# FLC-PCR_PCB_rev_1.net
KiCad netlist of a schematic drawn in EAGLE
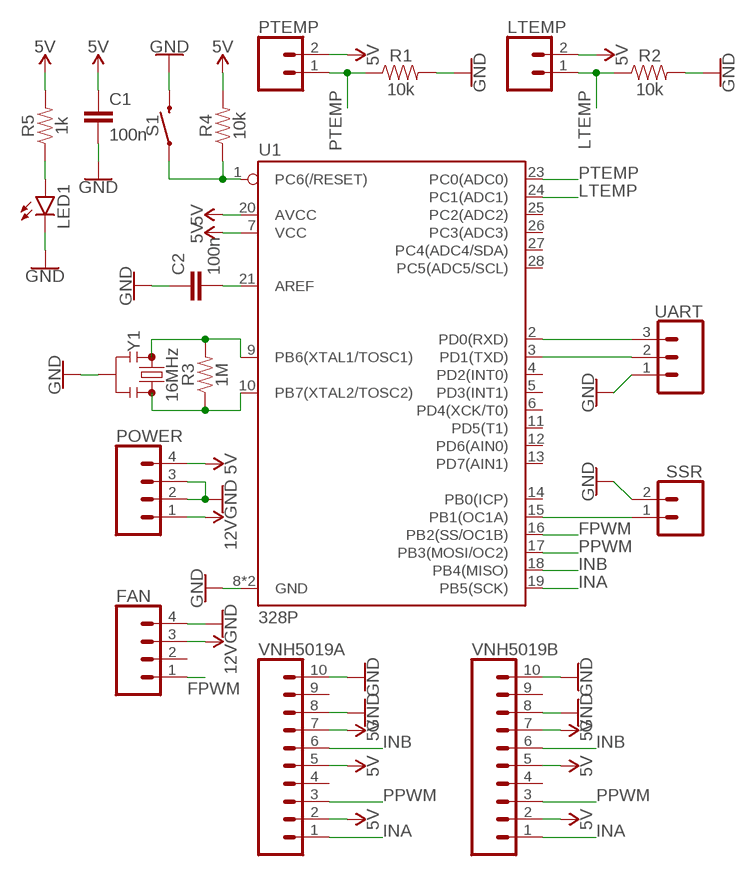
[diagram p0: schematic, sheet 1]

(export (version "E")
  (design (tool "Eeschema 10.0.6"))
  (components
    (comp (ref "C1")
      (value "100n")
      (footprint "eagle-import:C025-050X050")
      (libsource (lib "eagle-import") (part "C-EU025-050X050"))
    )
    (comp (ref "C2")
      (value "100n")
      (footprint "eagle-import:C025-050X050")
      (libsource (lib "eagle-import") (part "C-EU025-050X050"))
    )
    (comp (ref "FAN")
      (value "CONN_04PTH")
      (footprint "eagle-import:1X04")
      (libsource (lib "eagle-import") (part "CONN_04PTH"))
    )
    (comp (ref "LED1")
      (value "LED5MM")
      (footprint "eagle-import:LED5MM")
      (libsource (lib "eagle-import") (part "LED5MM"))
    )
    (comp (ref "LTEMP")
      (value "CONN_02")
      (footprint "eagle-import:1X02")
      (libsource (lib "eagle-import") (part "CONN_02"))
    )
    (comp (ref "POWER")
      (value "CONN_04PTH")
      (footprint "eagle-import:1X04")
      (libsource (lib "eagle-import") (part "CONN_04PTH"))
    )
    (comp (ref "PTEMP")
      (value "CONN_02")
      (footprint "eagle-import:1X02")
      (libsource (lib "eagle-import") (part "CONN_02"))
    )
    (comp (ref "R1")
      (value "10k")
      (footprint "eagle-import:AXIAL-0.3")
      (libsource (lib "eagle-import") (part "10KOHM-HORIZ-1/4W-1%"))
    )
    (comp (ref "R2")
      (value "10k")
      (footprint "eagle-import:AXIAL-0.3")
      (libsource (lib "eagle-import") (part "10KOHM-HORIZ-1/4W-1%"))
    )
    (comp (ref "R3")
      (value "1M")
      (footprint "eagle-import:AXIAL-0.3")
      (libsource (lib "eagle-import") (part "1MOHM-HORIZ-1/4W-5%"))
    )
    (comp (ref "R4")
      (value "10k")
      (footprint "eagle-import:AXIAL-0.3")
      (libsource (lib "eagle-import") (part "10KOHM-HORIZ-1/4W-1%"))
    )
    (comp (ref "R5")
      (value "1k")
      (footprint "eagle-import:AXIAL-0.3")
      (libsource (lib "eagle-import") (part "1KOHM-HORIZ-1/4W-1%"))
    )
    (comp (ref "S1")
      (value "MOMENTARY-SWITCH-SPST-PTH-6.0MM")
      (footprint "eagle-import:TACTILE_SWITCH_PTH_6.0MM")
      (libsource (lib "eagle-import") (part "MOMENTARY-SWITCH-SPST-PTH-6.0MM"))
    )
    (comp (ref "SSR")
      (value "CONN_02")
      (footprint "eagle-import:1X02")
      (libsource (lib "eagle-import") (part "CONN_02"))
    )
    (comp (ref "U1")
      (value "328P")
      (footprint "eagle-import:DIP28")
      (libsource (lib "eagle-import") (part "ATMEGA328P_PDIP"))
    )
    (comp (ref "UART")
      (value "CONN_03")
      (footprint "eagle-import:1X03")
      (libsource (lib "eagle-import") (part "CONN_03"))
    )
    (comp (ref "VNH5019A")
      (value "CONN_10\"")
      (footprint "eagle-import:1X10")
      (libsource (lib "eagle-import") (part "CONN_10{dblquote}"))
    )
    (comp (ref "VNH5019B")
      (value "CONN_10\"")
      (footprint "eagle-import:1X10")
      (libsource (lib "eagle-import") (part "CONN_10{dblquote}"))
    )
    (comp (ref "Y1")
      (value "16MHz")
      (footprint "eagle-import:RESONATOR-PTH-7.6X3.8")
      (libsource (lib "eagle-import") (part "RESONATORPTH-7.6X3.8"))
    )
  )
  (nets
    (net (code "1") (name "/FPWM") (class "Default")
      (node (ref "FAN") (pin "1") (pinfunction "1_1") (pintype "passive"))
      (node (ref "U1") (pin "16") (pinfunction "PB2(SS/OC1B)_16") (pintype "bidirectional"))
    )
    (net (code "2") (name "/INA") (class "Default")
      (node (ref "U1") (pin "19") (pinfunction "PB5(SCK)_19") (pintype "bidirectional"))
      (node (ref "VNH5019A") (pin "1") (pinfunction "1_1") (pintype "passive"))
      (node (ref "VNH5019B") (pin "1") (pinfunction "1_1") (pintype "passive"))
    )
    (net (code "3") (name "/INB") (class "Default")
      (node (ref "U1") (pin "18") (pinfunction "PB4(MISO)_18") (pintype "bidirectional"))
      (node (ref "VNH5019A") (pin "6") (pinfunction "6_6") (pintype "passive"))
      (node (ref "VNH5019B") (pin "6") (pinfunction "6_6") (pintype "passive"))
    )
    (net (code "4") (name "/LTEMP") (class "Default")
      (node (ref "LTEMP") (pin "1") (pinfunction "1_1") (pintype "passive"))
      (node (ref "R2") (pin "P$1") (pinfunction "1_P$1") (pintype "passive"))
      (node (ref "U1") (pin "24") (pinfunction "PC1(ADC1)_24") (pintype "bidirectional"))
    )
    (net (code "5") (name "/PPWM") (class "Default")
      (node (ref "U1") (pin "17") (pinfunction "PB3(MOSI/OC2)_17") (pintype "bidirectional"))
      (node (ref "VNH5019A") (pin "3") (pinfunction "3_3") (pintype "passive"))
      (node (ref "VNH5019B") (pin "3") (pinfunction "3_3") (pintype "passive"))
    )
    (net (code "6") (name "/PTEMP") (class "Default")
      (node (ref "PTEMP") (pin "1") (pinfunction "1_1") (pintype "passive"))
      (node (ref "R1") (pin "P$1") (pinfunction "1_P$1") (pintype "passive"))
      (node (ref "U1") (pin "23") (pinfunction "PC0(ADC0)_23") (pintype "bidirectional"))
    )
    (net (code "7") (name "5V") (class "Default")
      (node (ref "C1") (pin "1") (pinfunction "1_1") (pintype "passive"))
      (node (ref "LTEMP") (pin "2") (pinfunction "2_2") (pintype "passive"))
      (node (ref "POWER") (pin "4") (pinfunction "4_4") (pintype "passive"))
      (node (ref "PTEMP") (pin "2") (pinfunction "2_2") (pintype "passive"))
      (node (ref "R4") (pin "P$2") (pinfunction "2_P$2") (pintype "passive"))
      (node (ref "R5") (pin "P$2") (pinfunction "2_P$2") (pintype "passive"))
      (node (ref "U1") (pin "20") (pinfunction "AVCC_20") (pintype "bidirectional"))
      (node (ref "U1") (pin "7") (pinfunction "VCC_7") (pintype "bidirectional"))
      (node (ref "VNH5019A") (pin "2") (pinfunction "2_2") (pintype "passive"))
      (node (ref "VNH5019A") (pin "5") (pinfunction "5_5") (pintype "passive"))
      (node (ref "VNH5019A") (pin "7") (pinfunction "7_7") (pintype "passive"))
      (node (ref "VNH5019B") (pin "2") (pinfunction "2_2") (pintype "passive"))
      (node (ref "VNH5019B") (pin "5") (pinfunction "5_5") (pintype "passive"))
      (node (ref "VNH5019B") (pin "7") (pinfunction "7_7") (pintype "passive"))
    )
    (net (code "8") (name "12V") (class "Default")
      (node (ref "FAN") (pin "3") (pinfunction "3_3") (pintype "passive"))
      (node (ref "POWER") (pin "1") (pinfunction "1_1") (pintype "passive"))
    )
    (net (code "9") (name "GND") (class "Default")
      (node (ref "C1") (pin "2") (pinfunction "2_2") (pintype "passive"))
      (node (ref "C2") (pin "1") (pinfunction "1_1") (pintype "passive"))
      (node (ref "FAN") (pin "4") (pinfunction "4_4") (pintype "passive"))
      (node (ref "LED1") (pin "K") (pinfunction "C_K") (pintype "passive"))
      (node (ref "POWER") (pin "2") (pinfunction "2_2") (pintype "passive"))
      (node (ref "POWER") (pin "3") (pinfunction "3_3") (pintype "passive"))
      (node (ref "R1") (pin "P$2") (pinfunction "2_P$2") (pintype "passive"))
      (node (ref "R2") (pin "P$2") (pinfunction "2_P$2") (pintype "passive"))
      (node (ref "S1") (pin "3") (pinfunction "2_3") (pintype "passive"))
      (node (ref "SSR") (pin "2") (pinfunction "2_2") (pintype "passive"))
      (node (ref "U1") (pin "22") (pinfunction "GND_22") (pintype "bidirectional"))
      (node (ref "U1") (pin "8") (pinfunction "GND_8") (pintype "bidirectional"))
      (node (ref "UART") (pin "1") (pinfunction "1_1") (pintype "passive"))
      (node (ref "VNH5019A") (pin "10") (pinfunction "10_10") (pintype "passive"))
      (node (ref "VNH5019A") (pin "8") (pinfunction "8_8") (pintype "passive"))
      (node (ref "VNH5019B") (pin "10") (pinfunction "10_10") (pintype "passive"))
      (node (ref "VNH5019B") (pin "8") (pinfunction "8_8") (pintype "passive"))
      (node (ref "Y1") (pin "2") (pinfunction "2_2") (pintype "passive"))
    )
    (net (code "10") (name "Net-(R3-1)") (class "Default")
      (node (ref "R3") (pin "P$1") (pinfunction "1_P$1") (pintype "passive"))
      (node (ref "U1") (pin "10") (pinfunction "PB7(XTAL2/TOSC2)_10") (pintype "bidirectional"))
      (node (ref "Y1") (pin "3") (pinfunction "3_3") (pintype "passive"))
    )
    (net (code "11") (name "Net-(R3-2)") (class "Default")
      (node (ref "R3") (pin "P$2") (pinfunction "2_P$2") (pintype "passive"))
      (node (ref "U1") (pin "9") (pinfunction "PB6(XTAL1/TOSC1)_9") (pintype "bidirectional"))
      (node (ref "Y1") (pin "1") (pinfunction "1_1") (pintype "passive"))
    )
    (net (code "12") (name "Net-(R4-1)") (class "Default")
      (node (ref "R4") (pin "P$1") (pinfunction "1_P$1") (pintype "passive"))
      (node (ref "S1") (pin "1") (pinfunction "1_1") (pintype "passive"))
      (node (ref "U1") (pin "1") (pinfunction "PC6(/RESET)_1") (pintype "bidirectional"))
    )
    (net (code "13") (name "Net-(R5-1)") (class "Default")
      (node (ref "LED1") (pin "A") (pinfunction "A_A") (pintype "passive"))
      (node (ref "R5") (pin "P$1") (pinfunction "1_P$1") (pintype "passive"))
    )
    (net (code "14") (name "Net-(U1-AREF)") (class "Default")
      (node (ref "C2") (pin "2") (pinfunction "2_2") (pintype "passive"))
      (node (ref "U1") (pin "21") (pinfunction "AREF_21") (pintype "bidirectional"))
    )
    (net (code "15") (name "Net-(U1-PB1(OC1A))") (class "Default")
      (node (ref "SSR") (pin "1") (pinfunction "1_1") (pintype "passive"))
      (node (ref "U1") (pin "15") (pinfunction "PB1(OC1A)_15") (pintype "bidirectional"))
    )
    (net (code "16") (name "Net-(U1-PD0(RXD))") (class "Default")
      (node (ref "U1") (pin "2") (pinfunction "PD0(RXD)_2") (pintype "bidirectional"))
      (node (ref "UART") (pin "3") (pinfunction "3_3") (pintype "passive"))
    )
    (net (code "17") (name "Net-(U1-PD1(TXD))") (class "Default")
      (node (ref "U1") (pin "3") (pinfunction "PD1(TXD)_3") (pintype "bidirectional"))
      (node (ref "UART") (pin "2") (pinfunction "2_2") (pintype "passive"))
    )
    (net (code "18") (name "unconnected-(FAN-Pad2)") (class "Default")
      (node (ref "FAN") (pin "2") (pinfunction "2_2") (pintype "passive"))
    )
    (net (code "19") (name "unconnected-(U1-PB0(ICP)-Pad14)") (class "Default")
      (node (ref "U1") (pin "14") (pinfunction "PB0(ICP)_14") (pintype "bidirectional"))
    )
    (net (code "20") (name "unconnected-(U1-PC2(ADC2)-Pad25)") (class "Default")
      (node (ref "U1") (pin "25") (pinfunction "PC2(ADC2)_25") (pintype "bidirectional"))
    )
    (net (code "21") (name "unconnected-(U1-PC3(ADC3)-Pad26)") (class "Default")
      (node (ref "U1") (pin "26") (pinfunction "PC3(ADC3)_26") (pintype "bidirectional"))
    )
    (net (code "22") (name "unconnected-(U1-PC4(ADC4{slash}SDA)-Pad27)") (class "Default")
      (node (ref "U1") (pin "27") (pinfunction "PC4(ADC4/SDA)_27") (pintype "bidirectional"))
    )
    (net (code "23") (name "unconnected-(U1-PC5(ADC5{slash}SCL)-Pad28)") (class "Default")
      (node (ref "U1") (pin "28") (pinfunction "PC5(ADC5/SCL)_28") (pintype "bidirectional"))
    )
    (net (code "24") (name "unconnected-(U1-PD2(INT0)-Pad4)") (class "Default")
      (node (ref "U1") (pin "4") (pinfunction "PD2(INT0)_4") (pintype "bidirectional"))
    )
    (net (code "25") (name "unconnected-(U1-PD3(INT1)-Pad5)") (class "Default")
      (node (ref "U1") (pin "5") (pinfunction "PD3(INT1)_5") (pintype "bidirectional"))
    )
    (net (code "26") (name "unconnected-(U1-PD4(XCK{slash}T0)-Pad6)") (class "Default")
      (node (ref "U1") (pin "6") (pinfunction "PD4(XCK/T0)_6") (pintype "bidirectional"))
    )
    (net (code "27") (name "unconnected-(U1-PD5(T1)-Pad11)") (class "Default")
      (node (ref "U1") (pin "11") (pinfunction "PD5(T1)_11") (pintype "bidirectional"))
    )
    (net (code "28") (name "unconnected-(U1-PD6(AIN0)-Pad12)") (class "Default")
      (node (ref "U1") (pin "12") (pinfunction "PD6(AIN0)_12") (pintype "bidirectional"))
    )
    (net (code "29") (name "unconnected-(U1-PD7(AIN1)-Pad13)") (class "Default")
      (node (ref "U1") (pin "13") (pinfunction "PD7(AIN1)_13") (pintype "bidirectional"))
    )
    (net (code "30") (name "unconnected-(VNH5019A-Pad4)") (class "Default")
      (node (ref "VNH5019A") (pin "4") (pinfunction "4_4") (pintype "passive"))
    )
    (net (code "31") (name "unconnected-(VNH5019A-Pad9)") (class "Default")
      (node (ref "VNH5019A") (pin "9") (pinfunction "9_9") (pintype "passive"))
    )
    (net (code "32") (name "unconnected-(VNH5019B-Pad4)") (class "Default")
      (node (ref "VNH5019B") (pin "4") (pinfunction "4_4") (pintype "passive"))
    )
    (net (code "33") (name "unconnected-(VNH5019B-Pad9)") (class "Default")
      (node (ref "VNH5019B") (pin "9") (pinfunction "9_9") (pintype "passive"))
    )
  )
)
